# Acoustics_Board.net
KiCad netlist of a schematic drawn in Altium Designer
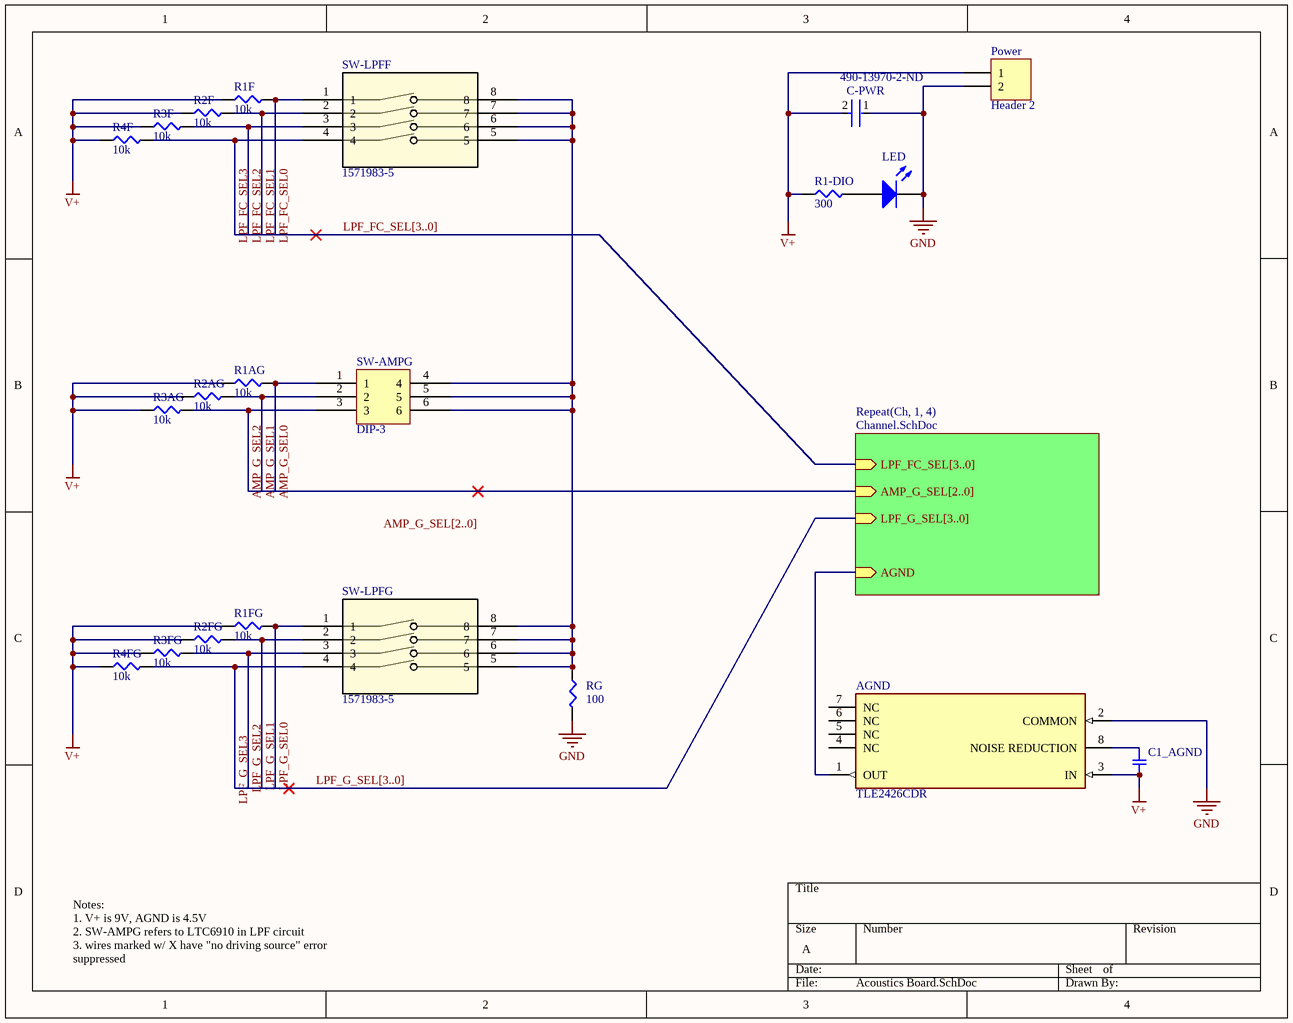
[diagram p0: Acoustics Board.SchDoc]

(export (version "E")
  (design (tool "Eeschema 10.0.6"))
  (components
    (comp (ref "AGND")
      (value "TLE2426CDR")
      (footprint "FP-D0008A-IPC_B")
      (description "Ground Reference (Virtual) Voltage Reference IC Adjustable 2V 20 VV ±1% 20 mA 8-SOIC")
      (fields
        (field (name "MANUFACTURER") "Texas Instruments")
        (field (name "MANUFACTURER PART NUMBER") "TLE2426MD")
      )
      (libsource (lib "Altium Content Vault") (part "6a05ed44ac4318f8a6b310f721958da"))
    )
    (comp (ref "C-PWR")
      (value "GRM31CR60J227ME11L")
      (footprint "FP-GRM31C-0_3-e0_3_0_9-IPC_C")
      (description "Chip Multilayer Ceramic Capacitors for General Purpose, 1206, 220uF, X5R, 15%, 20%, 6.3V")
      (fields
        (field (name "TOLERANCE") "20%")
        (field (name "SUPPLIER PART NUMBER 1") "490-13970-2-ND")
        (field (name "MANUFACTURER") "Murata")
      )
      (libsource (lib "Altium Content Vault") (part "f23184f103b6ebe33a8c269c53dcba6"))
    )
    (comp (ref "C1_AGND")
      (value "1µF")
      (footprint "SMD-0805C")
      (fields
        (field (name "MANUFACTURER") "KEMET")
        (field (name "MANUFACTURER PART NUMBER") "C0805C105K3RAC7800")
      )
      (libsource (lib "capacitor_murata_0805") (part "GCJ219R71C105KA01D"))
    )
    (comp (ref "LED")
      (value "150080SS75000")
      (footprint "0805_A")
      (description "Red 630nm LED Indication - Discrete 1.9V 0805 (2012 Metric)")
      (fields (field (name "MANUFACTURER") "Wuerth Elektronik"))
      (libsource (lib "Altium Content Vault") (part "WE-LED_K1A2-2"))
    )
    (comp (ref "Power")
      (value "Header 2")
      (footprint "HDR1X2")
      (libsource (lib "Miscellaneous Connectors") (part "Header 2"))
    )
    (comp (ref "R1-DIO")
      (value "300")
      (footprint "SMD-0805-RES")
      (fields
        (field (name "MANUFACTURER") "Stackpole Electronics Inc")
        (field (name "MANUFACTURER PART NUMBER") "RNCF0805DTE300R")
      )
      (libsource (lib "Panasonic_resistor_0805") (part "ERJ-6ENF1002V"))
    )
    (comp (ref "R1AG")
      (value "10k")
      (footprint "SMD-0805-RES")
      (fields
        (field (name "MANUFACTURER") "Panasonic Electronic Components")
        (field (name "MANUFACTURER PART NUMBER") "RMCF0805JG10K0")
      )
      (libsource (lib "Panasonic_resistor_0805") (part "ERJ-6ENF1002V"))
    )
    (comp (ref "R1F")
      (value "10k")
      (footprint "SMD-0805-RES")
      (fields
        (field (name "MANUFACTURER") "Panasonic Electronic Components")
        (field (name "MANUFACTURER PART NUMBER") "RMCF0805JG10K0")
      )
      (libsource (lib "Panasonic_resistor_0805") (part "ERJ-6ENF1002V"))
    )
    (comp (ref "R1FG")
      (value "10k")
      (footprint "SMD-0805-RES")
      (fields
        (field (name "MANUFACTURER") "Panasonic Electronic Components")
        (field (name "MANUFACTURER PART NUMBER") "RMCF0805JG10K0")
      )
      (libsource (lib "Panasonic_resistor_0805") (part "ERJ-6ENF1002V"))
    )
    (comp (ref "R2AG")
      (value "10k")
      (footprint "SMD-0805-RES")
      (fields
        (field (name "MANUFACTURER") "Panasonic Electronic Components")
        (field (name "MANUFACTURER PART NUMBER") "RMCF0805JG10K0")
      )
      (libsource (lib "Panasonic_resistor_0805") (part "ERJ-6ENF1002V"))
    )
    (comp (ref "R2F")
      (value "10k")
      (footprint "SMD-0805-RES")
      (fields
        (field (name "MANUFACTURER") "Panasonic Electronic Components")
        (field (name "MANUFACTURER PART NUMBER") "RMCF0805JG10K0")
      )
      (libsource (lib "Panasonic_resistor_0805") (part "ERJ-6ENF1002V"))
    )
    (comp (ref "R2FG")
      (value "10k")
      (footprint "SMD-0805-RES")
      (fields
        (field (name "MANUFACTURER") "Panasonic Electronic Components")
        (field (name "MANUFACTURER PART NUMBER") "RMCF0805JG10K0")
      )
      (libsource (lib "Panasonic_resistor_0805") (part "ERJ-6ENF1002V"))
    )
    (comp (ref "R3AG")
      (value "10k")
      (footprint "SMD-0805-RES")
      (fields
        (field (name "MANUFACTURER") "Panasonic Electronic Components")
        (field (name "MANUFACTURER PART NUMBER") "RMCF0805JG10K0")
      )
      (libsource (lib "Panasonic_resistor_0805") (part "ERJ-6ENF1002V"))
    )
    (comp (ref "R3F")
      (value "10k")
      (footprint "SMD-0805-RES")
      (fields
        (field (name "MANUFACTURER") "Panasonic Electronic Components")
        (field (name "MANUFACTURER PART NUMBER") "RMCF0805JG10K0")
      )
      (libsource (lib "Panasonic_resistor_0805") (part "ERJ-6ENF1002V"))
    )
    (comp (ref "R3FG")
      (value "10k")
      (footprint "SMD-0805-RES")
      (fields
        (field (name "MANUFACTURER") "Panasonic Electronic Components")
        (field (name "MANUFACTURER PART NUMBER") "RMCF0805JG10K0")
      )
      (libsource (lib "Panasonic_resistor_0805") (part "ERJ-6ENF1002V"))
    )
    (comp (ref "R4F")
      (value "10k")
      (footprint "SMD-0805-RES")
      (fields
        (field (name "MANUFACTURER") "Panasonic Electronic Components")
        (field (name "MANUFACTURER PART NUMBER") "RMCF0805JG10K0")
      )
      (libsource (lib "Panasonic_resistor_0805") (part "ERJ-6ENF1002V"))
    )
    (comp (ref "R4FG")
      (value "10k")
      (footprint "SMD-0805-RES")
      (fields
        (field (name "MANUFACTURER") "Panasonic Electronic Components")
        (field (name "MANUFACTURER PART NUMBER") "RMCF0805JG10K0")
      )
      (libsource (lib "Panasonic_resistor_0805") (part "ERJ-6ENF1002V"))
    )
    (comp (ref "RG")
      (value "100")
      (footprint "SMD-0805-RES")
      (description "RES SMD 100 OHM 1% 1/2W 0805")
      (fields
        (field (name "PART NUMBER") "ERJ-P06F1000V")
        (field (name "DIGI-KEY PART NUMBER") "P16057CT-ND")
      )
      (libsource (lib "Panasonic_resistor_0805") (part "ERJ-P06F1000V"))
    )
    (comp (ref "SW-AMPG") (value "DIP-3") (footprint "DIP6") (libsource (lib "acoustics-lib") (part "DIP-3")))
    (comp (ref "SW-LPFF")
      (value "1571983-5")
      (footprint "SW4_1571983_4P_TEC")
      (description "No Description Available")
      (fields (field (name "COPYRIGHT") "Copyright (C) 2022 Ultra Librarian. All rights reserved."))
      (libsource (lib "1571983-5") (part "1571983-5"))
    )
    (comp (ref "SW-LPFG")
      (value "1571983-5")
      (footprint "SW4_1571983_4P_TEC")
      (description "No Description Available")
      (fields (field (name "COPYRIGHT") "Copyright (C) 2022 Ultra Librarian. All rights reserved."))
      (libsource (lib "1571983-5") (part "1571983-5"))
    )
  )
  (nets
    (net (code "1") (name "/AGND") (class "Default")
      (node (ref "AGND") (pin "1") (pinfunction "OUT_1") (pintype "output"))
    )
    (net (code "2") (name "/AMP_G_SEL0") (class "Default")
      (node (ref "R1AG") (pin "2") (pinfunction "2_2") (pintype "passive"))
      (node (ref "SW-AMPG") (pin "1") (pinfunction "1_1") (pintype "passive"))
    )
    (net (code "3") (name "/AMP_G_SEL1") (class "Default")
      (node (ref "R2AG") (pin "2") (pinfunction "2_2") (pintype "passive"))
      (node (ref "SW-AMPG") (pin "2") (pinfunction "2_2") (pintype "passive"))
    )
    (net (code "4") (name "/AMP_G_SEL2") (class "Default")
      (node (ref "R3AG") (pin "2") (pinfunction "2_2") (pintype "passive"))
      (node (ref "SW-AMPG") (pin "3") (pinfunction "3_3") (pintype "passive"))
    )
    (net (code "7") (name "/LPF_FC_SEL0") (class "Default")
      (node (ref "R1F") (pin "2") (pinfunction "2_2") (pintype "passive"))
      (node (ref "SW-LPFF") (pin "1") (pinfunction "1_1") (pintype "passive"))
    )
    (net (code "8") (name "/LPF_FC_SEL1") (class "Default")
      (node (ref "R2F") (pin "2") (pinfunction "2_2") (pintype "passive"))
      (node (ref "SW-LPFF") (pin "2") (pinfunction "2_2") (pintype "passive"))
    )
    (net (code "9") (name "/LPF_FC_SEL2") (class "Default")
      (node (ref "R3F") (pin "2") (pinfunction "2_2") (pintype "passive"))
      (node (ref "SW-LPFF") (pin "3") (pinfunction "3_3") (pintype "passive"))
    )
    (net (code "10") (name "/LPF_FC_SEL3") (class "Default")
      (node (ref "R4F") (pin "2") (pinfunction "2_2") (pintype "passive"))
      (node (ref "SW-LPFF") (pin "4") (pinfunction "4_4") (pintype "passive"))
    )
    (net (code "12") (name "/LPF_G_SEL0") (class "Default")
      (node (ref "R1FG") (pin "2") (pinfunction "2_2") (pintype "passive"))
      (node (ref "SW-LPFG") (pin "1") (pinfunction "1_1") (pintype "passive"))
    )
    (net (code "13") (name "/LPF_G_SEL1") (class "Default")
      (node (ref "R2FG") (pin "2") (pinfunction "2_2") (pintype "passive"))
      (node (ref "SW-LPFG") (pin "2") (pinfunction "2_2") (pintype "passive"))
    )
    (net (code "14") (name "/LPF_G_SEL2") (class "Default")
      (node (ref "R3FG") (pin "2") (pinfunction "2_2") (pintype "passive"))
      (node (ref "SW-LPFG") (pin "3") (pinfunction "3_3") (pintype "passive"))
    )
    (net (code "15") (name "/LPF_G_SEL3") (class "Default")
      (node (ref "R4FG") (pin "2") (pinfunction "2_2") (pintype "passive"))
      (node (ref "SW-LPFG") (pin "4") (pinfunction "4_4") (pintype "passive"))
    )
    (net (code "17") (name "GND") (class "Default")
      (node (ref "AGND") (pin "2") (pinfunction "COMMON_2") (pintype "input"))
      (node (ref "C-PWR") (pin "1") (pinfunction "1_1") (pintype "passive"))
      (node (ref "LED") (pin "1") (pinfunction "K_1") (pintype "passive"))
      (node (ref "Power") (pin "2") (pinfunction "2_2") (pintype "passive"))
      (node (ref "RG") (pin "2") (pinfunction "2_2") (pintype "passive"))
    )
    (net (code "18") (name "Net-(AGND-NOISE_REDUCTION)") (class "Default")
      (node (ref "AGND") (pin "8") (pinfunction "NOISE_REDUCTION_8") (pintype "passive"))
      (node (ref "C1_AGND") (pin "1") (pinfunction "1_1") (pintype "passive"))
    )
    (net (code "19") (name "Net-(LED-A)") (class "Default")
      (node (ref "LED") (pin "2") (pinfunction "A_2") (pintype "passive"))
      (node (ref "R1-DIO") (pin "2") (pinfunction "2_2") (pintype "passive"))
    )
    (net (code "20") (name "Net-(RG-Pad1)") (class "Default")
      (node (ref "RG") (pin "1") (pinfunction "1_1") (pintype "passive"))
      (node (ref "SW-AMPG") (pin "4") (pinfunction "4_4") (pintype "passive"))
      (node (ref "SW-AMPG") (pin "5") (pinfunction "5_5") (pintype "passive"))
      (node (ref "SW-AMPG") (pin "6") (pinfunction "6_6") (pintype "passive"))
      (node (ref "SW-LPFF") (pin "5") (pinfunction "5_5") (pintype "passive"))
      (node (ref "SW-LPFF") (pin "6") (pinfunction "6_6") (pintype "passive"))
      (node (ref "SW-LPFF") (pin "7") (pinfunction "7_7") (pintype "passive"))
      (node (ref "SW-LPFF") (pin "8") (pinfunction "8_8") (pintype "passive"))
      (node (ref "SW-LPFG") (pin "5") (pinfunction "5_5") (pintype "passive"))
      (node (ref "SW-LPFG") (pin "6") (pinfunction "6_6") (pintype "passive"))
      (node (ref "SW-LPFG") (pin "7") (pinfunction "7_7") (pintype "passive"))
      (node (ref "SW-LPFG") (pin "8") (pinfunction "8_8") (pintype "passive"))
    )
    (net (code "21") (name "V+") (class "Default")
      (node (ref "AGND") (pin "3") (pinfunction "IN_3") (pintype "input"))
      (node (ref "C-PWR") (pin "2") (pinfunction "2_2") (pintype "passive"))
      (node (ref "C1_AGND") (pin "2") (pinfunction "2_2") (pintype "passive"))
      (node (ref "Power") (pin "1") (pinfunction "1_1") (pintype "passive"))
      (node (ref "R1-DIO") (pin "1") (pinfunction "1_1") (pintype "passive"))
      (node (ref "R1AG") (pin "1") (pinfunction "1_1") (pintype "passive"))
      (node (ref "R1F") (pin "1") (pinfunction "1_1") (pintype "passive"))
      (node (ref "R1FG") (pin "1") (pinfunction "1_1") (pintype "passive"))
      (node (ref "R2AG") (pin "1") (pinfunction "1_1") (pintype "passive"))
      (node (ref "R2F") (pin "1") (pinfunction "1_1") (pintype "passive"))
      (node (ref "R2FG") (pin "1") (pinfunction "1_1") (pintype "passive"))
      (node (ref "R3AG") (pin "1") (pinfunction "1_1") (pintype "passive"))
      (node (ref "R3F") (pin "1") (pinfunction "1_1") (pintype "passive"))
      (node (ref "R3FG") (pin "1") (pinfunction "1_1") (pintype "passive"))
      (node (ref "R4F") (pin "1") (pinfunction "1_1") (pintype "passive"))
      (node (ref "R4FG") (pin "1") (pinfunction "1_1") (pintype "passive"))
    )
    (net (code "22") (name "unconnected-(AGND-NC-Pad4)") (class "Default")
      (node (ref "AGND") (pin "4") (pinfunction "NC_4") (pintype "passive"))
    )
    (net (code "23") (name "unconnected-(AGND-NC-Pad5)") (class "Default")
      (node (ref "AGND") (pin "5") (pinfunction "NC_5") (pintype "passive"))
    )
    (net (code "24") (name "unconnected-(AGND-NC-Pad6)") (class "Default")
      (node (ref "AGND") (pin "6") (pinfunction "NC_6") (pintype "passive"))
    )
    (net (code "25") (name "unconnected-(AGND-NC-Pad7)") (class "Default")
      (node (ref "AGND") (pin "7") (pinfunction "NC_7") (pintype "passive"))
    )
  )
)
